# Sheet1.net
KiCad netlist of a schematic drawn in Altium Designer
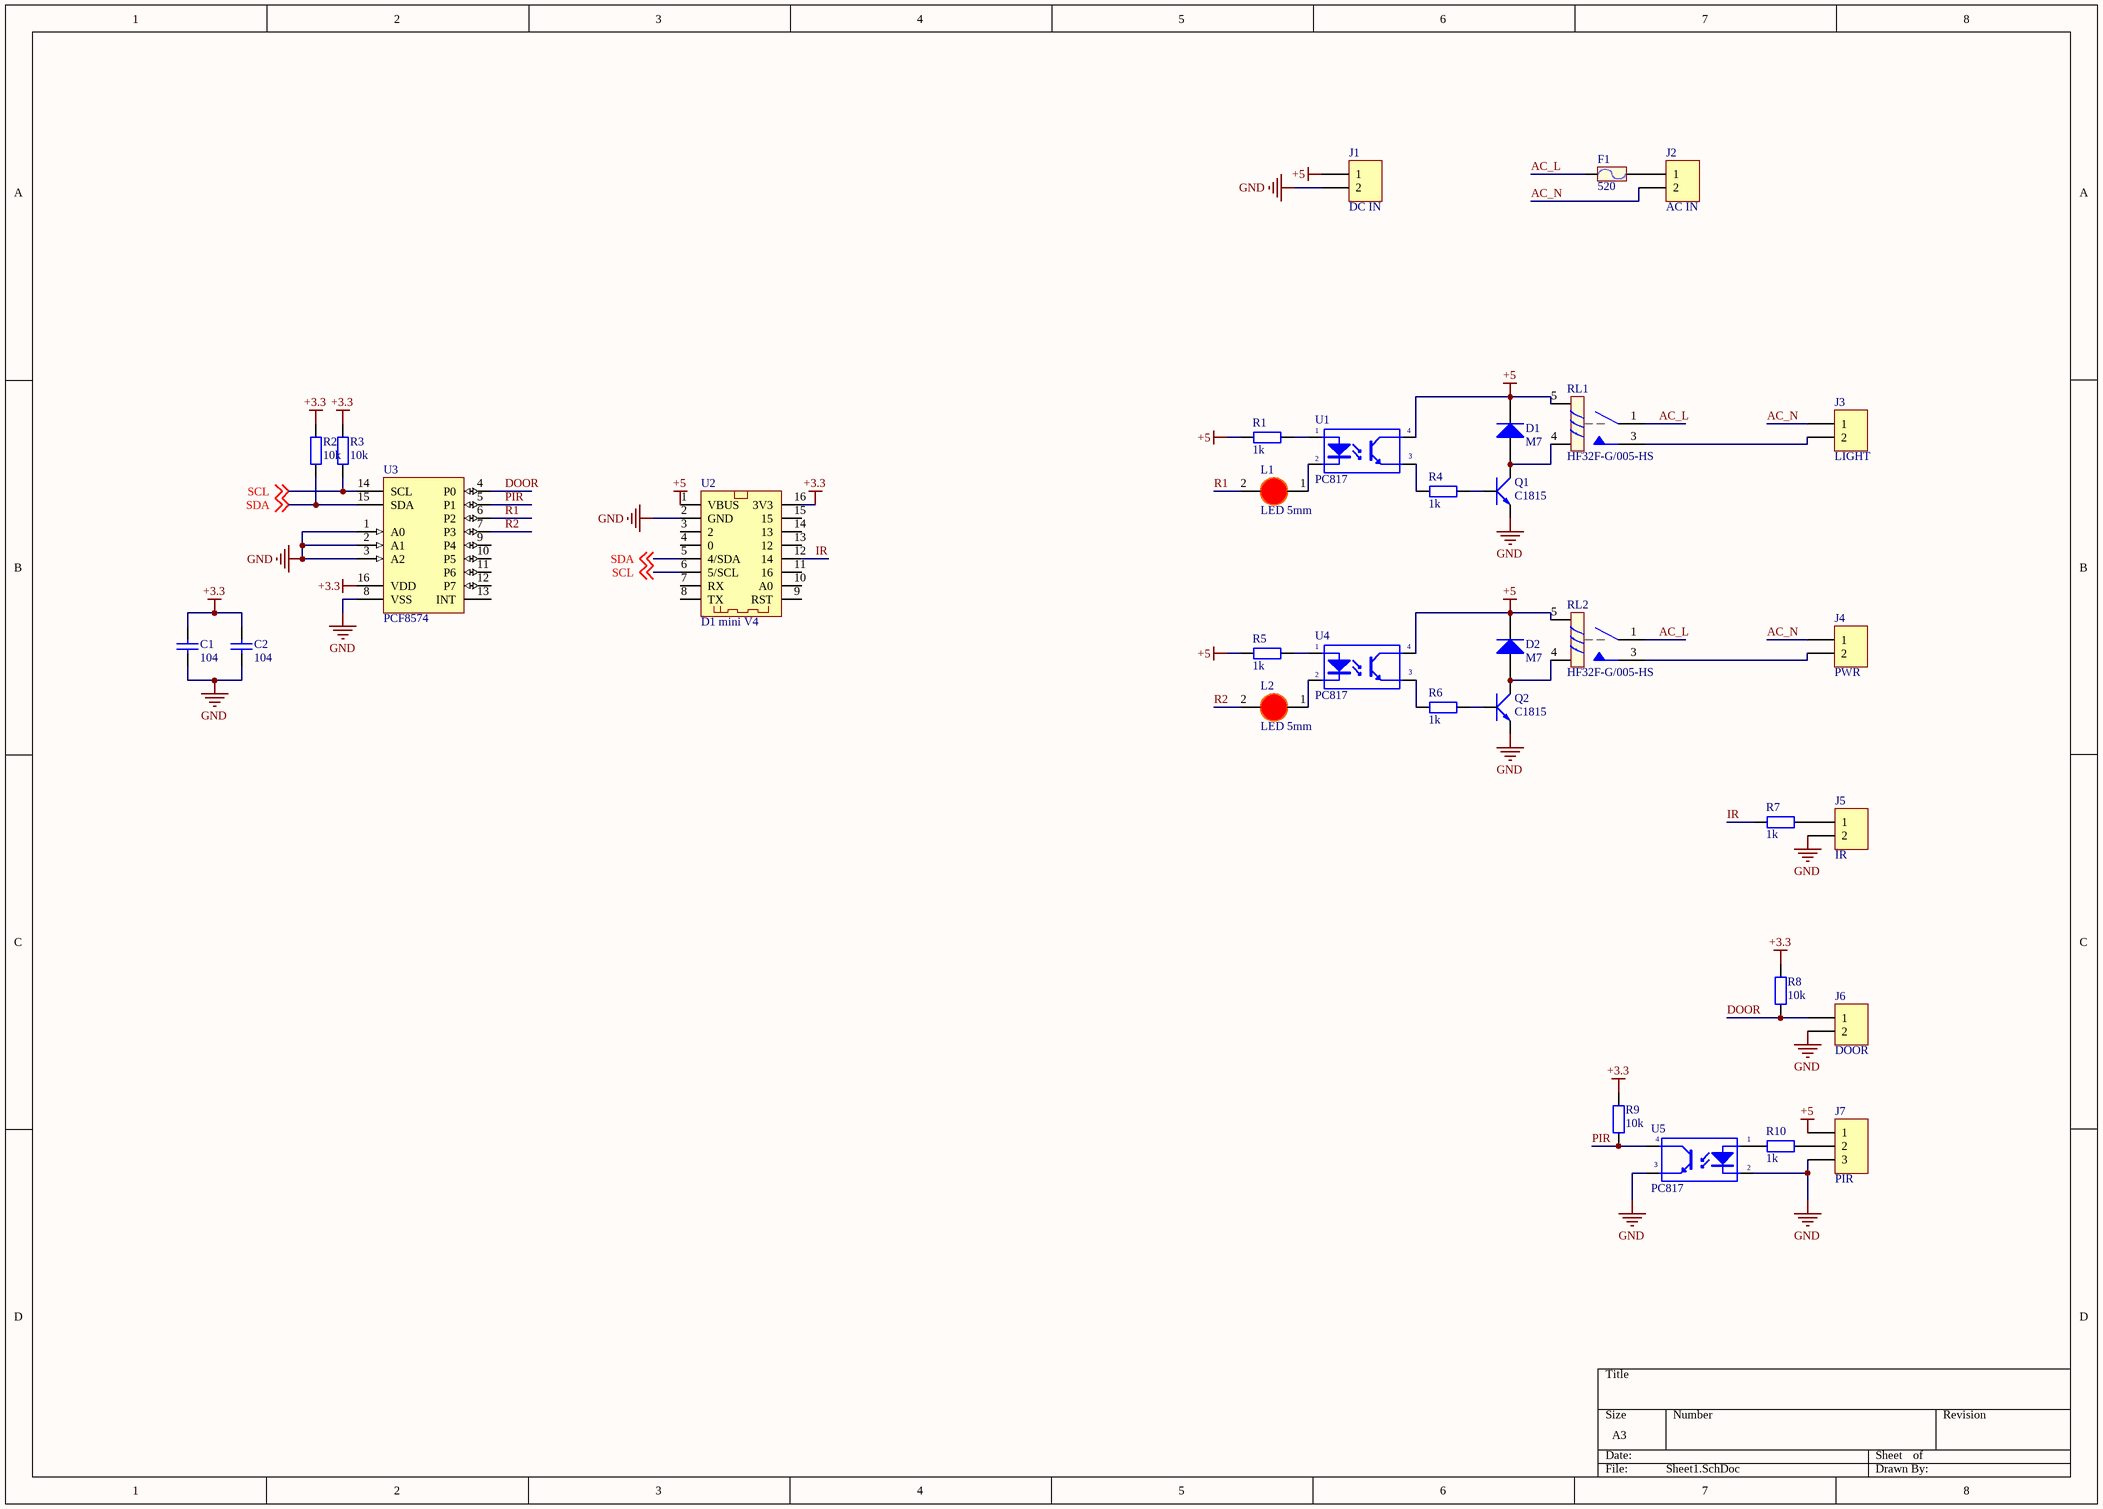
[diagram p0: Sheet1.SchDoc]

(export (version "E")
  (design (tool "Eeschema 10.0.6"))
  (components
    (comp (ref "C1")
      (value "104")
      (footprint "tu 0805")
      (description "Dán")
      (libsource (lib "Altium_Lib_by_KhueNguyenCreator") (part "Tu 0805 104 50V 10%"))
    )
    (comp (ref "C2")
      (value "104")
      (footprint "tu 0805")
      (description "Dán")
      (libsource (lib "Altium_Lib_by_KhueNguyenCreator") (part "Tu 0805 104 50V 10%"))
    )
    (comp (ref "D1")
      (value "M7")
      (footprint "DIODE SMA")
      (description "Dán")
      (libsource (lib "Altium_Lib_by_KhueNguyenCreator") (part "Diode M7 ( 4007 )"))
    )
    (comp (ref "D2")
      (value "M7")
      (footprint "DIODE SMA")
      (description "Dán")
      (libsource (lib "Altium_Lib_by_KhueNguyenCreator") (part "Diode M7 ( 4007 )"))
    )
    (comp (ref "F1")
      (value "520")
      (footprint "De Cau Chi 520 630")
      (description "5x20mm")
      (libsource (lib "Altium_Lib_by_KhueNguyenCreator") (part "De Cau Chi 520 630"))
    )
    (comp (ref "J1")
      (value "DC IN")
      (footprint "CON 2 HT3.96")
      (description "CON2 KF terminal")
      (libsource (lib "iuh-thuc-hanh") (part "CON 2 EDG"))
    )
    (comp (ref "J2")
      (value "AC IN")
      (footprint "CON 2 2EDG5.08 B")
      (description "CON2 KF terminal")
      (libsource (lib "iuh-thuc-hanh") (part "CON 2 EDG"))
    )
    (comp (ref "J3")
      (value "LIGHT")
      (footprint "CON 2 2EDG5.08 B")
      (description "CON2 KF terminal")
      (libsource (lib "iuh-thuc-hanh") (part "CON 2 EDG"))
    )
    (comp (ref "J4")
      (value "PWR")
      (footprint "CON 2 2EDG5.08 B")
      (description "CON2 KF terminal")
      (libsource (lib "iuh-thuc-hanh") (part "CON 2 EDG"))
    )
    (comp (ref "J5")
      (value "IR")
      (footprint "CON 2 HT3.96")
      (description "CON2 KF terminal")
      (libsource (lib "iuh-thuc-hanh") (part "CON 2 EDG"))
    )
    (comp (ref "J6")
      (value "DOOR")
      (footprint "CON 2 HT3.96")
      (description "CON2 KF terminal")
      (libsource (lib "iuh-thuc-hanh") (part "CON 2 EDG"))
    )
    (comp (ref "J7")
      (value "PIR")
      (footprint "KF3-3.96")
      (description "CON3 KF terminal")
      (libsource (lib "iuh-thuc-hanh") (part "CON 3 EDG"))
    )
    (comp (ref "L1")
      (value "LED 5mm")
      (footprint "LED-5MM-RED")
      (description "Cắm")
      (libsource (lib "Altium_Lib_by_KhueNguyenCreator") (part "LED 5mm Do"))
    )
    (comp (ref "L2")
      (value "LED 5mm")
      (footprint "LED-5MM-RED")
      (description "Cắm")
      (libsource (lib "Altium_Lib_by_KhueNguyenCreator") (part "LED 5mm Do"))
    )
    (comp (ref "Q1")
      (value "C1815")
      (footprint "TO92")
      (description "NPN transistor")
      (libsource (lib "Altium_Lib_by_KhueNguyenCreator") (part "Trans C1815 DIP"))
    )
    (comp (ref "Q2")
      (value "C1815")
      (footprint "TO92")
      (description "NPN transistor")
      (libsource (lib "Altium_Lib_by_KhueNguyenCreator") (part "Trans C1815 DIP"))
    )
    (comp (ref "R1")
      (value "1k")
      (footprint "tro smd 0805")
      (description "Dán")
      (libsource (lib "Altium_Lib_by_KhueNguyenCreator") (part "Tro 0805 1% 1k"))
    )
    (comp (ref "R2")
      (value "10k")
      (footprint "tro smd 0805")
      (description "Dán")
      (libsource (lib "Altium_Lib_by_KhueNguyenCreator") (part "Tro 0805 1% 10k"))
    )
    (comp (ref "R3")
      (value "10k")
      (footprint "tro smd 0805")
      (description "Dán")
      (libsource (lib "Altium_Lib_by_KhueNguyenCreator") (part "Tro 0805 1% 10k"))
    )
    (comp (ref "R4")
      (value "1k")
      (footprint "tro smd 0805")
      (description "Dán")
      (libsource (lib "Altium_Lib_by_KhueNguyenCreator") (part "Tro 0805 1% 1k"))
    )
    (comp (ref "R5")
      (value "1k")
      (footprint "tro smd 0805")
      (description "Dán")
      (libsource (lib "Altium_Lib_by_KhueNguyenCreator") (part "Tro 0805 1% 1k"))
    )
    (comp (ref "R6")
      (value "1k")
      (footprint "tro smd 0805")
      (description "Dán")
      (libsource (lib "Altium_Lib_by_KhueNguyenCreator") (part "Tro 0805 1% 1k"))
    )
    (comp (ref "R7")
      (value "1k")
      (footprint "tro smd 0805")
      (description "Dán")
      (libsource (lib "Altium_Lib_by_KhueNguyenCreator") (part "Tro 0805 1% 1k"))
    )
    (comp (ref "R8")
      (value "10k")
      (footprint "tro smd 0805")
      (description "Dán")
      (libsource (lib "Altium_Lib_by_KhueNguyenCreator") (part "Tro 0805 1% 10k"))
    )
    (comp (ref "R9")
      (value "10k")
      (footprint "tro smd 0805")
      (description "Dán")
      (libsource (lib "Altium_Lib_by_KhueNguyenCreator") (part "Tro 0805 1% 10k"))
    )
    (comp (ref "R10")
      (value "1k")
      (footprint "tro smd 0805")
      (description "Dán")
      (libsource (lib "Altium_Lib_by_KhueNguyenCreator") (part "Tro 0805 1% 1k"))
    )
    (comp (ref "RL1")
      (value "HF32F-G/005-HS")
      (footprint "HF32F-G")
      (description "Relay hongfa 10A 4P HF32F-G/005-HS")
      (libsource (lib "iuh-thuc-hanh") (part "Relay HF 10A"))
    )
    (comp (ref "RL2")
      (value "HF32F-G/005-HS")
      (footprint "HF32F-G")
      (description "Relay hongfa 10A 4P HF32F-G/005-HS")
      (libsource (lib "iuh-thuc-hanh") (part "Relay HF 10A"))
    )
    (comp (ref "U1")
      (value "PC817")
      (footprint "DIP4")
      (description "Single Opto")
      (libsource (lib "LIBRARY1") (part "PC817"))
    )
    (comp (ref "U2")
      (value "D1 mini V4")
      (footprint "WEMOS D1 MINI V4 USD")
      (description "ESP8266 D1")
      (libsource (lib "iuh-thuc-hanh") (part "Wemos D1 mini V4.0"))
    )
    (comp (ref "U3") (value "PCF8574") (footprint "DIP16") (libsource (lib "iuh-thuc-hanh") (part "PCF8574")))
    (comp (ref "U4")
      (value "PC817")
      (footprint "DIP4")
      (description "Single Opto")
      (libsource (lib "LIBRARY1") (part "PC817"))
    )
    (comp (ref "U5")
      (value "PC817")
      (footprint "DIP4")
      (description "Single Opto")
      (libsource (lib "LIBRARY1") (part "PC817"))
    )
  )
  (nets
    (net (code "1") (name "+3.3") (class "Default")
      (node (ref "C1") (pin "1") (pinfunction "1_1") (pintype "passive"))
      (node (ref "C2") (pin "1") (pinfunction "1_1") (pintype "passive"))
      (node (ref "R2") (pin "2") (pinfunction "2_2") (pintype "passive"))
      (node (ref "R3") (pin "2") (pinfunction "2_2") (pintype "passive"))
      (node (ref "R8") (pin "2") (pinfunction "2_2") (pintype "passive"))
      (node (ref "R9") (pin "2") (pinfunction "2_2") (pintype "passive"))
      (node (ref "U2") (pin "16") (pinfunction "3V3_16") (pintype "passive"))
      (node (ref "U3") (pin "16") (pinfunction "VDD_16") (pintype "passive"))
    )
    (net (code "2") (name "+5") (class "Default")
      (node (ref "D1") (pin "2") (pinfunction "K_2") (pintype "passive"))
      (node (ref "D2") (pin "2") (pinfunction "K_2") (pintype "passive"))
      (node (ref "J1") (pin "1") (pinfunction "1_1") (pintype "passive"))
      (node (ref "J7") (pin "1") (pinfunction "1_1") (pintype "passive"))
      (node (ref "R1") (pin "1") (pinfunction "1_1") (pintype "passive"))
      (node (ref "R5") (pin "1") (pinfunction "1_1") (pintype "passive"))
      (node (ref "RL1") (pin "5") (pinfunction "5_5") (pintype "passive"))
      (node (ref "RL2") (pin "5") (pinfunction "5_5") (pintype "passive"))
      (node (ref "U1") (pin "4") (pinfunction "C_4") (pintype "passive"))
      (node (ref "U2") (pin "1") (pinfunction "VBUS_1") (pintype "passive"))
      (node (ref "U4") (pin "4") (pinfunction "C_4") (pintype "passive"))
    )
    (net (code "3") (name "/AC_L") (class "Default")
      (node (ref "F1") (pin "1") (pinfunction "1_1") (pintype "passive"))
      (node (ref "RL1") (pin "1") (pinfunction "1_1") (pintype "passive"))
      (node (ref "RL2") (pin "1") (pinfunction "1_1") (pintype "passive"))
    )
    (net (code "4") (name "/AC_N") (class "Default")
      (node (ref "J2") (pin "2") (pinfunction "2_2") (pintype "passive"))
      (node (ref "J3") (pin "1") (pinfunction "1_1") (pintype "passive"))
      (node (ref "J4") (pin "1") (pinfunction "1_1") (pintype "passive"))
    )
    (net (code "5") (name "/DOOR") (class "Default")
      (node (ref "J6") (pin "1") (pinfunction "1_1") (pintype "passive"))
      (node (ref "R8") (pin "1") (pinfunction "1_1") (pintype "passive"))
      (node (ref "U3") (pin "4") (pinfunction "P0_4") (pintype "bidirectional"))
    )
    (net (code "6") (name "/IR") (class "Default")
      (node (ref "R7") (pin "1") (pinfunction "1_1") (pintype "passive"))
      (node (ref "U2") (pin "12") (pinfunction "14_12") (pintype "passive"))
    )
    (net (code "7") (name "/PIR") (class "Default")
      (node (ref "R9") (pin "1") (pinfunction "1_1") (pintype "passive"))
      (node (ref "U3") (pin "5") (pinfunction "P1_5") (pintype "bidirectional"))
      (node (ref "U5") (pin "4") (pinfunction "C_4") (pintype "passive"))
    )
    (net (code "8") (name "/R1") (class "Default")
      (node (ref "L1") (pin "2") (pinfunction "K_2") (pintype "passive"))
      (node (ref "U3") (pin "6") (pinfunction "P2_6") (pintype "bidirectional"))
    )
    (net (code "9") (name "/R2") (class "Default")
      (node (ref "L2") (pin "2") (pinfunction "K_2") (pintype "passive"))
      (node (ref "U3") (pin "7") (pinfunction "P3_7") (pintype "bidirectional"))
    )
    (net (code "10") (name "GND") (class "Default")
      (node (ref "C1") (pin "2") (pinfunction "2_2") (pintype "passive"))
      (node (ref "C2") (pin "2") (pinfunction "2_2") (pintype "passive"))
      (node (ref "J1") (pin "2") (pinfunction "2_2") (pintype "passive"))
      (node (ref "J5") (pin "2") (pinfunction "2_2") (pintype "passive"))
      (node (ref "J6") (pin "2") (pinfunction "2_2") (pintype "passive"))
      (node (ref "J7") (pin "3") (pinfunction "3_3") (pintype "passive"))
      (node (ref "Q1") (pin "1") (pinfunction "E_1") (pintype "passive"))
      (node (ref "Q2") (pin "1") (pinfunction "E_1") (pintype "passive"))
      (node (ref "U2") (pin "2") (pinfunction "GND_2") (pintype "passive"))
      (node (ref "U3") (pin "1") (pinfunction "A0_1") (pintype "input"))
      (node (ref "U3") (pin "2") (pinfunction "A1_2") (pintype "input"))
      (node (ref "U3") (pin "3") (pinfunction "A2_3") (pintype "input"))
      (node (ref "U3") (pin "8") (pinfunction "VSS_8") (pintype "passive"))
      (node (ref "U5") (pin "2") (pinfunction "K_2") (pintype "passive"))
      (node (ref "U5") (pin "3") (pinfunction "E_3") (pintype "passive"))
    )
    (net (code "11") (name "Net-(D1-A)") (class "Default")
      (node (ref "D1") (pin "1") (pinfunction "A_1") (pintype "passive"))
      (node (ref "Q1") (pin "2") (pinfunction "C_2") (pintype "passive"))
      (node (ref "RL1") (pin "4") (pinfunction "4_4") (pintype "passive"))
    )
    (net (code "12") (name "Net-(D2-A)") (class "Default")
      (node (ref "D2") (pin "1") (pinfunction "A_1") (pintype "passive"))
      (node (ref "Q2") (pin "2") (pinfunction "C_2") (pintype "passive"))
      (node (ref "RL2") (pin "4") (pinfunction "4_4") (pintype "passive"))
    )
    (net (code "13") (name "Net-(F1-Pad2)") (class "Default")
      (node (ref "F1") (pin "2") (pinfunction "2_2") (pintype "passive"))
      (node (ref "J2") (pin "1") (pinfunction "1_1") (pintype "passive"))
    )
    (net (code "14") (name "Net-(J3-Pad2)") (class "Default")
      (node (ref "J3") (pin "2") (pinfunction "2_2") (pintype "passive"))
      (node (ref "RL1") (pin "3") (pinfunction "3_3") (pintype "passive"))
    )
    (net (code "15") (name "Net-(J4-Pad2)") (class "Default")
      (node (ref "J4") (pin "2") (pinfunction "2_2") (pintype "passive"))
      (node (ref "RL2") (pin "3") (pinfunction "3_3") (pintype "passive"))
    )
    (net (code "16") (name "Net-(J5-Pad1)") (class "Default")
      (node (ref "J5") (pin "1") (pinfunction "1_1") (pintype "passive"))
      (node (ref "R7") (pin "2") (pinfunction "2_2") (pintype "passive"))
    )
    (net (code "17") (name "Net-(J7-Pad2)") (class "Default")
      (node (ref "J7") (pin "2") (pinfunction "2_2") (pintype "passive"))
      (node (ref "R10") (pin "1") (pinfunction "1_1") (pintype "passive"))
    )
    (net (code "18") (name "Net-(L1-A)") (class "Default")
      (node (ref "L1") (pin "1") (pinfunction "A_1") (pintype "passive"))
      (node (ref "U1") (pin "2") (pinfunction "K_2") (pintype "passive"))
    )
    (net (code "19") (name "Net-(L2-A)") (class "Default")
      (node (ref "L2") (pin "1") (pinfunction "A_1") (pintype "passive"))
      (node (ref "U4") (pin "2") (pinfunction "K_2") (pintype "passive"))
    )
    (net (code "20") (name "Net-(Q1-B)") (class "Default")
      (node (ref "Q1") (pin "3") (pinfunction "B_3") (pintype "passive"))
      (node (ref "R4") (pin "2") (pinfunction "2_2") (pintype "passive"))
    )
    (net (code "21") (name "Net-(Q2-B)") (class "Default")
      (node (ref "Q2") (pin "3") (pinfunction "B_3") (pintype "passive"))
      (node (ref "R6") (pin "2") (pinfunction "2_2") (pintype "passive"))
    )
    (net (code "22") (name "Net-(U1-A)") (class "Default")
      (node (ref "R1") (pin "2") (pinfunction "2_2") (pintype "passive"))
      (node (ref "U1") (pin "1") (pinfunction "A_1") (pintype "passive"))
    )
    (net (code "23") (name "Net-(U1-E)") (class "Default")
      (node (ref "R4") (pin "1") (pinfunction "1_1") (pintype "passive"))
      (node (ref "U1") (pin "3") (pinfunction "E_3") (pintype "passive"))
    )
    (net (code "24") (name "Net-(U4-A)") (class "Default")
      (node (ref "R5") (pin "2") (pinfunction "2_2") (pintype "passive"))
      (node (ref "U4") (pin "1") (pinfunction "A_1") (pintype "passive"))
    )
    (net (code "25") (name "Net-(U4-E)") (class "Default")
      (node (ref "R6") (pin "1") (pinfunction "1_1") (pintype "passive"))
      (node (ref "U4") (pin "3") (pinfunction "E_3") (pintype "passive"))
    )
    (net (code "26") (name "Net-(U5-A)") (class "Default")
      (node (ref "R10") (pin "2") (pinfunction "2_2") (pintype "passive"))
      (node (ref "U5") (pin "1") (pinfunction "A_1") (pintype "passive"))
    )
    (net (code "27") (name "SCL") (class "Default")
      (node (ref "R3") (pin "1") (pinfunction "1_1") (pintype "passive"))
      (node (ref "U2") (pin "6") (pinfunction "5/SCL_6") (pintype "passive"))
      (node (ref "U3") (pin "14") (pinfunction "SCL_14") (pintype "passive"))
    )
    (net (code "28") (name "SDA") (class "Default")
      (node (ref "R2") (pin "1") (pinfunction "1_1") (pintype "passive"))
      (node (ref "U2") (pin "5") (pinfunction "4/SDA_5") (pintype "passive"))
      (node (ref "U3") (pin "15") (pinfunction "SDA_15") (pintype "passive"))
    )
    (net (code "29") (name "unconnected-(U2-0-Pad4)") (class "Default")
      (node (ref "U2") (pin "4") (pinfunction "0_4") (pintype "passive"))
    )
    (net (code "30") (name "unconnected-(U2-2-Pad3)") (class "Default")
      (node (ref "U2") (pin "3") (pinfunction "2_3") (pintype "passive"))
    )
    (net (code "31") (name "unconnected-(U2-12-Pad13)") (class "Default")
      (node (ref "U2") (pin "13") (pinfunction "12_13") (pintype "passive"))
    )
    (net (code "32") (name "unconnected-(U2-13-Pad14)") (class "Default")
      (node (ref "U2") (pin "14") (pinfunction "13_14") (pintype "passive"))
    )
    (net (code "33") (name "unconnected-(U2-16-Pad11)") (class "Default")
      (node (ref "U2") (pin "11") (pinfunction "16_11") (pintype "passive"))
    )
    (net (code "34") (name "unconnected-(U2-A0-Pad10)") (class "Default")
      (node (ref "U2") (pin "10") (pinfunction "A0_10") (pintype "passive"))
    )
    (net (code "35") (name "unconnected-(U2-Pad15)") (class "Default")
      (node (ref "U2") (pin "15") (pinfunction "15_15") (pintype "passive"))
    )
    (net (code "36") (name "unconnected-(U2-RST-Pad9)") (class "Default")
      (node (ref "U2") (pin "9") (pinfunction "RST_9") (pintype "passive"))
    )
    (net (code "37") (name "unconnected-(U2-RX-Pad7)") (class "Default")
      (node (ref "U2") (pin "7") (pinfunction "RX_7") (pintype "passive"))
    )
    (net (code "38") (name "unconnected-(U2-TX-Pad8)") (class "Default")
      (node (ref "U2") (pin "8") (pinfunction "TX_8") (pintype "passive"))
    )
    (net (code "39") (name "unconnected-(U3-INT-Pad13)") (class "Default")
      (node (ref "U3") (pin "13") (pinfunction "INT_13") (pintype "passive"))
    )
    (net (code "40") (name "unconnected-(U3-P4-Pad9)") (class "Default")
      (node (ref "U3") (pin "9") (pinfunction "P4_9") (pintype "bidirectional"))
    )
    (net (code "41") (name "unconnected-(U3-P5-Pad10)") (class "Default")
      (node (ref "U3") (pin "10") (pinfunction "P5_10") (pintype "bidirectional"))
    )
    (net (code "42") (name "unconnected-(U3-P6-Pad11)") (class "Default")
      (node (ref "U3") (pin "11") (pinfunction "P6_11") (pintype "bidirectional"))
    )
    (net (code "43") (name "unconnected-(U3-P7-Pad12)") (class "Default")
      (node (ref "U3") (pin "12") (pinfunction "P7_12") (pintype "bidirectional"))
    )
  )
)
